# powersupply.net
KiCad netlist of a schematic drawn in Altium Designer
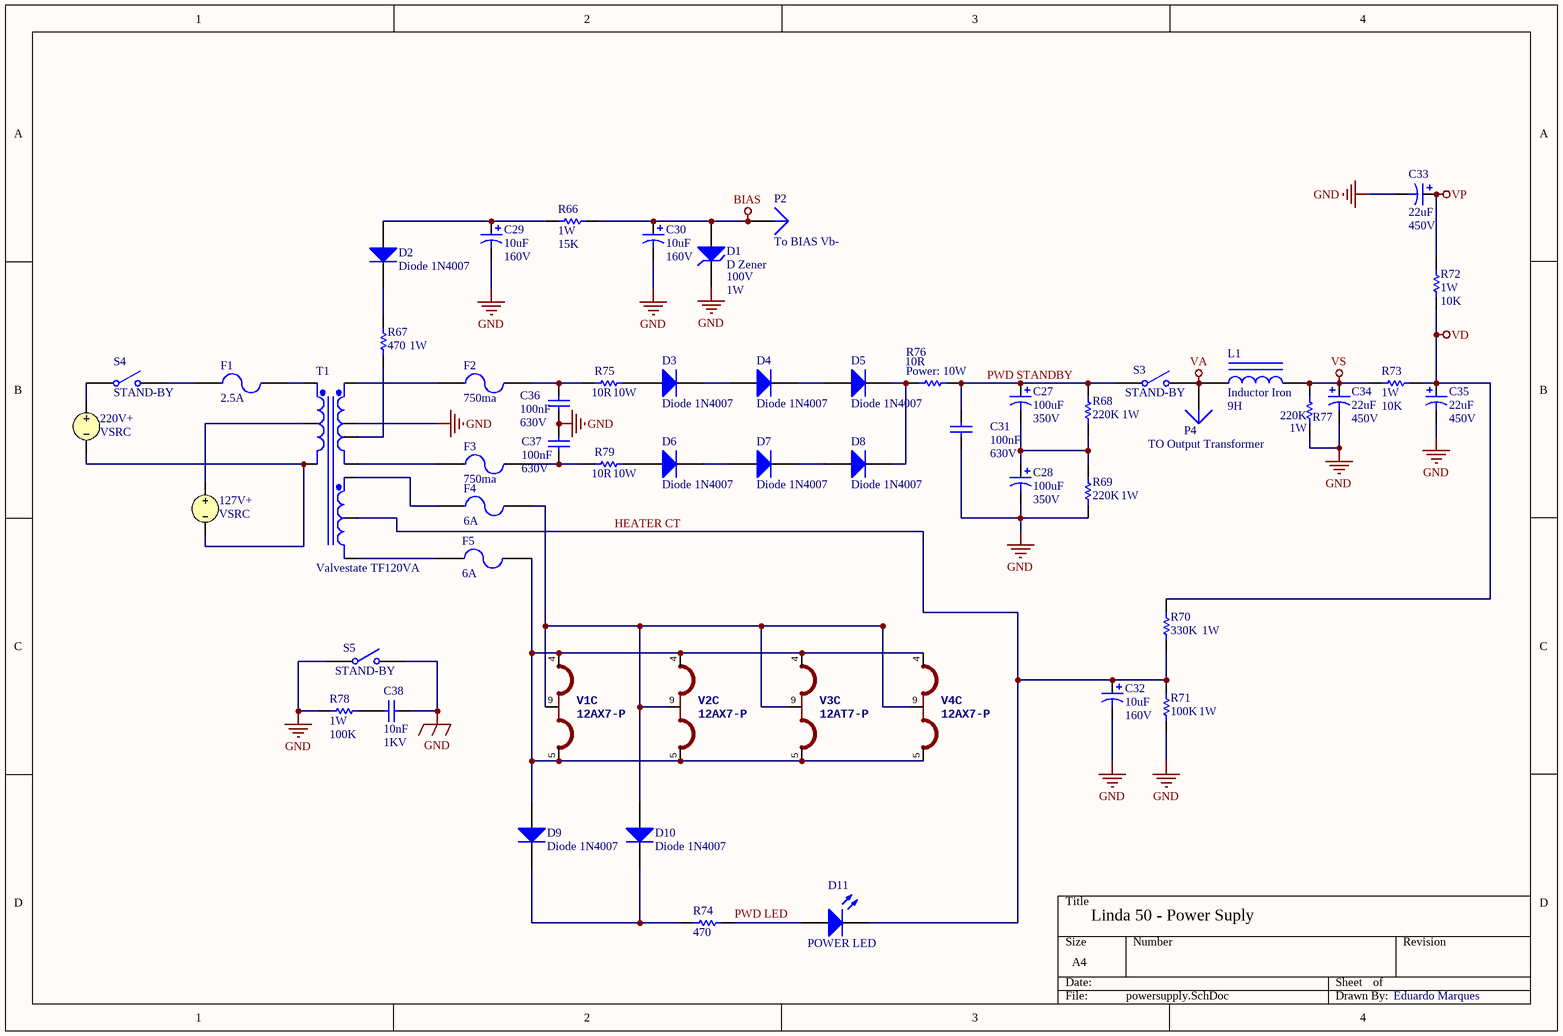
[diagram p0: powersupply.SchDoc]

(export (version "E")
  (design (tool "Eeschema 10.0.6"))
  (components
    (comp (ref "127V+")
      (value "VSRC")
      (description "Voltage Source")
      (fields (field (name "PUBLISHER") "Altium Limited"))
      (libsource (lib "Simulation Sources") (part "VSRC"))
    )
    (comp (ref "220V+")
      (value "VSRC")
      (description "Voltage Source")
      (fields (field (name "PUBLISHER") "Altium Limited"))
      (libsource (lib "Simulation Sources") (part "VSRC"))
    )
    (comp (ref "C27")
      (value "100uF")
      (footprint "FT Eletrolitic 100uF Axial")
      (description "FT Eletrolitic Polarized Capacitor Axial 100uF")
      (fields
        (field (name "VOLTAGE") "350V")
        (field (name "Comment") "Cap FT Eletrolitic 100uF Axial 350V")
        (field (name "PUBLISHER") "Whitesheep Amps")
      )
      (libsource (lib "capacitors") (part "Cap FT Eletrolitic 100uF Axial 350V"))
    )
    (comp (ref "C28")
      (value "100uF")
      (footprint "FT Eletrolitic 100uF Axial")
      (description "FT Eletrolitic Polarized Capacitor Axial 100uF")
      (fields
        (field (name "VOLTAGE") "350V")
        (field (name "Comment") "Cap FT Eletrolitic 100uF Axial 350V")
        (field (name "PUBLISHER") "Whitesheep Amps")
      )
      (libsource (lib "capacitors") (part "Cap FT Eletrolitic 100uF Axial 350V"))
    )
    (comp (ref "C29")
      (value "10uF")
      (footprint "RAD-POL-16x20x7.5")
      (description "Vishay 22uF 100V Polarized Capacitor (Radial); 2 Leads")
      (fields
        (field (name "PART NUMBER") "142 RHS")
        (field (name "VOLTAGE") "160V")
        (field (name "Comment") "Cap Pol Radial Vishay 22uF 100V")
        (field (name "PUBLISHER") "Altium Limited")
      )
      (libsource (lib "capacitors") (part "Cap Pol Radial Vishay 22uF 100V"))
    )
    (comp (ref "C30")
      (value "10uF")
      (footprint "RAD-POL-16x20x7.5")
      (description "Vishay 22uF 100V Polarized Capacitor (Radial); 2 Leads")
      (fields
        (field (name "PART NUMBER") "142 RHS")
        (field (name "VOLTAGE") "160V")
        (field (name "Comment") "Cap Pol Radial Vishay 22uF 100V")
        (field (name "PUBLISHER") "Altium Limited")
      )
      (libsource (lib "capacitors") (part "Cap Pol Radial Vishay 22uF 100V"))
    )
    (comp (ref "C31")
      (value "100nF")
      (footprint "CAP-XICON-100nF-630V")
      (description "Capacitor XICON (WINE COVER) Polypropilene CAP 630V")
      (fields
        (field (name "VOLTAGE") "630V")
        (field (name "Comment") "Orange Drop Capacitor")
        (field (name "PUBLISHER") "Altium Limited")
      )
      (libsource (lib "capacitors") (part "Cap-XICON-100nF-630V"))
    )
    (comp (ref "C32")
      (value "10uF")
      (footprint "RAD-POL-16x20x7.5")
      (description "Vishay 22uF 100V Polarized Capacitor (Radial); 2 Leads")
      (fields
        (field (name "PART NUMBER") "142 RHS")
        (field (name "VOLTAGE") "160V")
        (field (name "Comment") "Cap Pol Radial Vishay 22uF 100V")
        (field (name "PUBLISHER") "Altium Limited")
      )
      (libsource (lib "capacitors") (part "Cap Pol Radial Vishay 22uF 100V"))
    )
    (comp (ref "C33")
      (value "22uF")
      (footprint "RAD-POL-7.6-15")
      (description "Polarized Capacitor (Axial)")
      (fields
        (field (name "VOLTAGE") "450V")
        (field (name "Comment") "Cap Pol Rad")
        (field (name "PUBLISHER") "Altium Limited")
      )
      (libsource (lib "capacitors") (part "Cap Pol Rad"))
    )
    (comp (ref "C34")
      (value "22uF")
      (footprint "RAD-POL-7.6-15")
      (description "Polarized Capacitor (Axial)")
      (fields
        (field (name "VOLTAGE") "450V")
        (field (name "Comment") "Cap Pol Rad")
        (field (name "PUBLISHER") "Altium Limited")
      )
      (libsource (lib "capacitors") (part "Cap Pol Rad"))
    )
    (comp (ref "C35")
      (value "22uF")
      (footprint "RAD-POL-7.6-15")
      (description "Polarized Capacitor (Axial)")
      (fields
        (field (name "VOLTAGE") "450V")
        (field (name "Comment") "Cap Pol Rad")
        (field (name "PUBLISHER") "Altium Limited")
      )
      (libsource (lib "capacitors") (part "Cap Pol Rad"))
    )
    (comp (ref "C36")
      (value "100nF")
      (footprint "CAP-XICON-100nF-630V")
      (description "Capacitor XICON (WINE COVER) Polypropilene CAP 630V")
      (fields
        (field (name "VOLTAGE") "630V")
        (field (name "Comment") "Orange Drop Capacitor")
        (field (name "PUBLISHER") "Altium Limited")
      )
      (libsource (lib "capacitors") (part "Cap-XICON-100nF-630V"))
    )
    (comp (ref "C37")
      (value "100nF")
      (footprint "CAP-XICON-100nF-630V")
      (description "Capacitor XICON (WINE COVER) Polypropilene CAP 630V")
      (fields
        (field (name "VOLTAGE") "630V")
        (field (name "Comment") "Orange Drop Capacitor")
        (field (name "PUBLISHER") "Altium Limited")
      )
      (libsource (lib "capacitors") (part "Cap-XICON-100nF-630V"))
    )
    (comp (ref "C38")
      (value "10nF")
      (footprint "RAD-0.4")
      (description "Capacitor XICON (WINE COVER) Polypropilene CAP 630V")
      (fields
        (field (name "VOLTAGE") "1KV")
        (field (name "Comment") "Orange Drop Capacitor")
        (field (name "PUBLISHER") "Altium Limited")
      )
      (libsource (lib "capacitors") (part "Cap-XICON-100nF-630V"))
    )
    (comp (ref "D1")
      (value "D Zener")
      (footprint "ZENER 1W 100V")
      (description "Zener Diode")
      (fields
        (field (name "VOLTAGE") "100V")
        (field (name "POWER") "1W")
        (field (name "PUBLISHER") "Altium Limited")
      )
      (libsource (lib "Miscellaneous Devices") (part "D Zener"))
    )
    (comp (ref "D2")
      (value "Diode 1N4007")
      (footprint "DO-41")
      (description "1 Amp General Purpose Rectifier")
      (fields (field (name "PUBLISHER") "Altium Limited"))
      (libsource (lib "Miscellaneous Devices") (part "Diode 1N4007"))
    )
    (comp (ref "D3")
      (value "Diode 1N4007")
      (footprint "1N4007-10.46mm Diode")
      (description "1 Amp General Purpose Rectifier")
      (fields (field (name "PUBLISHER") "Altium Limited"))
      (libsource (lib "diodes") (part "Diode 1N4007"))
    )
    (comp (ref "D4")
      (value "Diode 1N4007")
      (footprint "1N4007-10.46mm Diode")
      (description "1 Amp General Purpose Rectifier")
      (fields (field (name "PUBLISHER") "Altium Limited"))
      (libsource (lib "diodes") (part "Diode 1N4007"))
    )
    (comp (ref "D5")
      (value "Diode 1N4007")
      (footprint "1N4007-10.46mm Diode")
      (description "1 Amp General Purpose Rectifier")
      (fields (field (name "PUBLISHER") "Altium Limited"))
      (libsource (lib "diodes") (part "Diode 1N4007"))
    )
    (comp (ref "D6")
      (value "Diode 1N4007")
      (footprint "1N4007-10.46mm Diode")
      (description "1 Amp General Purpose Rectifier")
      (fields (field (name "PUBLISHER") "Altium Limited"))
      (libsource (lib "diodes") (part "Diode 1N4007"))
    )
    (comp (ref "D7")
      (value "Diode 1N4007")
      (footprint "1N4007-10.46mm Diode")
      (description "1 Amp General Purpose Rectifier")
      (fields (field (name "PUBLISHER") "Altium Limited"))
      (libsource (lib "diodes") (part "Diode 1N4007"))
    )
    (comp (ref "D8")
      (value "Diode 1N4007")
      (footprint "1N4007-10.46mm Diode")
      (description "1 Amp General Purpose Rectifier")
      (fields (field (name "PUBLISHER") "Altium Limited"))
      (libsource (lib "diodes") (part "Diode 1N4007"))
    )
    (comp (ref "D9")
      (value "Diode 1N4007")
      (footprint "1N4007-10.46mm Diode")
      (description "1 Amp General Purpose Rectifier")
      (fields (field (name "PUBLISHER") "Altium Limited"))
      (libsource (lib "diodes") (part "Diode 1N4007"))
    )
    (comp (ref "D10")
      (value "Diode 1N4007")
      (footprint "1N4007-10.46mm Diode")
      (description "1 Amp General Purpose Rectifier")
      (fields (field (name "PUBLISHER") "Altium Limited"))
      (libsource (lib "diodes") (part "Diode 1N4007"))
    )
    (comp (ref "D11")
      (value "POWER LED")
      (footprint "LED-1")
      (description "Typical RED GaAs LED")
      (fields (field (name "PUBLISHER") "Altium Limited"))
      (libsource (lib "Miscellaneous Devices") (part "LED1"))
    )
    (comp (ref "F1")
      (value "2.5A")
      (footprint "PIN-W2/E2.8")
      (description "Fuse")
      (fields (field (name "PUBLISHER") "Altium Limited"))
      (libsource (lib "Miscellaneous Devices") (part "Fuse 2"))
    )
    (comp (ref "F2")
      (value "750ma")
      (footprint "FUSE-PCB-6x31")
      (description "Fuse")
      (fields (field (name "PUBLISHER") "Altium Limited"))
      (libsource (lib "fuses") (part "Fuse 2"))
    )
    (comp (ref "F3")
      (value "750ma")
      (footprint "FUSE-PCB-6x31")
      (description "Fuse")
      (fields (field (name "PUBLISHER") "Altium Limited"))
      (libsource (lib "fuses") (part "Fuse 2"))
    )
    (comp (ref "F4")
      (value "6A")
      (footprint "FUSE-PCB-6x31")
      (description "Fuse")
      (fields (field (name "PUBLISHER") "Altium Limited"))
      (libsource (lib "fuses") (part "Fuse 2"))
    )
    (comp (ref "F5")
      (value "6A")
      (footprint "FUSE-PCB-6x31")
      (description "Fuse")
      (fields (field (name "PUBLISHER") "Altium Limited"))
      (libsource (lib "fuses") (part "Fuse 2"))
    )
    (comp (ref "L1")
      (value "Inductor Iron")
      (footprint "AXIAL-0.9")
      (description "Magnetic-Core Inductor")
      (fields (field (name "ALTIUM_VALUE") "9H") (field (name "PUBLISHER") "Altium Limited"))
      (libsource (lib "Miscellaneous Devices") (part "Inductor Iron"))
    )
    (comp (ref "P2")
      (value "To BIAS Vb-")
      (footprint "PIN1")
      (description "Plug")
      (fields (field (name "PUBLISHER") "Altium Limited"))
      (libsource (lib "Miscellaneous Connectors") (part "Plug"))
    )
    (comp (ref "P4")
      (value "TO Output Transformer")
      (footprint "PIN1")
      (description "Plug")
      (fields (field (name "PUBLISHER") "Altium Limited"))
      (libsource (lib "Miscellaneous Connectors") (part "Plug"))
    )
    (comp (ref "R66")
      (value "15K")
      (footprint "AXIAL-0.6")
      (description "Semiconductor Resistor")
      (fields
        (field (name "POWER") "1W")
        (field (name "Comment") "Metal Film Resistor 1W")
        (field (name "PUBLISHER") "Linda Hand Buit Amplifiers")
      )
      (libsource (lib "resistors") (part "Res Wire Wound 1W"))
    )
    (comp (ref "R67")
      (value "470")
      (footprint "AXIAL-0.6")
      (description "Semiconductor Resistor")
      (fields
        (field (name "POWER") "1W")
        (field (name "Comment") "Metal Film Resistor 1W")
        (field (name "PUBLISHER") "Linda Hand Buit Amplifiers")
      )
      (libsource (lib "resistors") (part "Res Wire Wound 1W"))
    )
    (comp (ref "R68")
      (value "220K")
      (footprint "RESISTOR-MetalOxide-3W")
      (description "Semiconductor Resistor")
      (fields
        (field (name "POWER") "1W")
        (field (name "Comment") "Metal Film Resistor 1W")
        (field (name "PUBLISHER") "Linda Hand Buit Amplifiers")
      )
      (libsource (lib "resistors") (part "Res Wire Wound 1W"))
    )
    (comp (ref "R69")
      (value "220K")
      (footprint "RESISTOR-MetalOxide-3W")
      (description "Semiconductor Resistor")
      (fields
        (field (name "POWER") "1W")
        (field (name "Comment") "Metal Film Resistor 1W")
        (field (name "PUBLISHER") "Linda Hand Buit Amplifiers")
      )
      (libsource (lib "resistors") (part "Res Wire Wound 1W"))
    )
    (comp (ref "R70")
      (value "330K")
      (footprint "AXIAL-0.6")
      (description "Semiconductor Resistor")
      (fields
        (field (name "POWER") "1W")
        (field (name "Comment") "Metal Film Resistor 1W")
        (field (name "PUBLISHER") "Linda Hand Buit Amplifiers")
      )
      (libsource (lib "resistors") (part "Res Wire Wound 1W"))
    )
    (comp (ref "R71")
      (value "100K")
      (footprint "AXIAL-0.6")
      (description "Semiconductor Resistor")
      (fields
        (field (name "POWER") "1W")
        (field (name "Comment") "Metal Film Resistor 1W")
        (field (name "PUBLISHER") "Linda Hand Buit Amplifiers")
      )
      (libsource (lib "resistors") (part "Res Wire Wound 1W"))
    )
    (comp (ref "R72")
      (value "10K")
      (footprint "AXIAL-0.6")
      (description "Semiconductor Resistor")
      (fields
        (field (name "POWER") "1W")
        (field (name "Comment") "Metal Film Resistor 1W")
        (field (name "PUBLISHER") "Linda Hand Buit Amplifiers")
      )
      (libsource (lib "resistors") (part "Res Wire Wound 1W"))
    )
    (comp (ref "R73")
      (value "10K")
      (footprint "AXIAL-0.6")
      (description "Semiconductor Resistor")
      (fields
        (field (name "POWER") "1W")
        (field (name "Comment") "Metal Film Resistor 1W")
        (field (name "PUBLISHER") "Linda Hand Buit Amplifiers")
      )
      (libsource (lib "resistors") (part "Res Wire Wound 1W"))
    )
    (comp (ref "R74")
      (value "470")
      (footprint "AXIAL-0.6")
      (description "Semiconductor Resistor")
      (fields
        (field (name "POWER") "1/2W")
        (field (name "Comment") "Metal Film Resistor 1/2W")
        (field (name "PUBLISHER") "Whitesheep Amps")
      )
      (libsource (lib "resistors") (part "Res Metal Film 1/2W"))
    )
    (comp (ref "R75")
      (value "10R")
      (footprint "AXIAL-1.0")
      (description "Semiconductor Resistor")
      (fields
        (field (name "POWER") "10W")
        (field (name "Comment") "Wire Wound Power Resistor")
        (field (name "PUBLISHER") "Whitesheep Amps")
      )
      (libsource (lib "resistors") (part "Res Wire Wound Power Resistor 5W"))
    )
    (comp (ref "R76")
      (value "10R")
      (footprint "Power Wirewound Resistor 10W - Vishay Dale")
      (description "Semiconductor Resistor")
      (fields
        (field (name "POWER") "10W")
        (field (name "MANUFACTURER PART NUMBER") "RS01010R00FE73")
        (field (name "Comment") "Wire Wound Power Resistor")
        (field (name "PUBLISHER") "Whitesheep Amps")
      )
      (libsource (lib "resistors") (part "Res Vishay Dale Wire Wound Power Resistor 10R 10W"))
    )
    (comp (ref "R77")
      (value "220K")
      (footprint "RESISTOR-MetalOxide-3W")
      (description "Semiconductor Resistor")
      (fields
        (field (name "POWER") "1W")
        (field (name "Comment") "Metal Film Resistor 1W")
        (field (name "PUBLISHER") "Linda Hand Buit Amplifiers")
      )
      (libsource (lib "resistors") (part "Res Wire Wound 1W"))
    )
    (comp (ref "R78")
      (value "100K")
      (footprint "AXIAL-0.6")
      (description "Semiconductor Resistor")
      (fields
        (field (name "POWER") "1W")
        (field (name "Comment") "Metal Film Resistor 1W")
        (field (name "PUBLISHER") "Linda Hand Buit Amplifiers")
      )
      (libsource (lib "resistors") (part "Res Wire Wound 1W"))
    )
    (comp (ref "R79")
      (value "10R")
      (footprint "AXIAL-1.0")
      (description "Semiconductor Resistor")
      (fields
        (field (name "POWER") "10W")
        (field (name "Comment") "Wire Wound Power Resistor")
        (field (name "PUBLISHER") "Whitesheep Amps")
      )
      (libsource (lib "resistors") (part "Res Wire Wound Power Resistor 5W"))
    )
    (comp (ref "S3")
      (value "STAND-BY")
      (footprint "SPST-2")
      (description "Single-Pole, Single-Throw Switch")
      (fields (field (name "PUBLISHER") "Altium Limited"))
      (libsource (lib "Miscellaneous Devices") (part "SW-SPST"))
    )
    (comp (ref "S4")
      (value "STAND-BY")
      (footprint "SPST-2")
      (description "Single-Pole, Single-Throw Switch")
      (fields (field (name "PUBLISHER") "Altium Limited"))
      (libsource (lib "Miscellaneous Devices") (part "SW-SPST"))
    )
    (comp (ref "S5")
      (value "STAND-BY")
      (footprint "SPST-2")
      (description "Single-Pole, Single-Throw Switch")
      (fields (field (name "PUBLISHER") "Altium Limited"))
      (libsource (lib "Miscellaneous Devices") (part "SW-SPST"))
    )
    (comp (ref "T1")
      (value "Valvestate TF120VA")
      (footprint "TRF_5")
      (description "VALVESTATE TF 120VA")
      (fields (field (name "PUBLISHER") "LINDA Hand Built Amplifiers"))
      (libsource (lib "trafo") (part "Valvestate TF120VA"))
    )
    (comp (ref "V1")
      (value "12AX7-P")
      (footprint "NOVAL")
      (libsource (lib "eagle_tubes_v6") (part "12AX7-P"))
    )
    (comp (ref "V2")
      (value "12AX7-P")
      (footprint "NOVAL")
      (libsource (lib "eagle_tubes_v6") (part "12AX7-P"))
    )
    (comp (ref "V3")
      (value "12AT7-P")
      (footprint "NOVAL")
      (libsource (lib "eagle_tubes_v6") (part "12AT7-P"))
    )
    (comp (ref "V4")
      (value "12AX7-P")
      (footprint "NOVAL")
      (libsource (lib "eagle_tubes_v6") (part "12AX7-P"))
    )
  )
  (nets
    (net (code "1") (name "/HEATER CT") (class "Default")
      (node (ref "C32") (pin "1") (pinfunction "1_1") (pintype "passive"))
      (node (ref "D11") (pin "2") (pinfunction "K_2") (pintype "passive"))
      (node (ref "R70") (pin "1") (pinfunction "1_1") (pintype "passive"))
      (node (ref "R71") (pin "2") (pinfunction "2_2") (pintype "passive"))
      (node (ref "T1") (pin "9") (pinfunction "3.15V_CT_9") (pintype "passive"))
    )
    (net (code "3") (name "/PWD STANDBY") (class "Default")
      (node (ref "C27") (pin "1") (pinfunction "1_1") (pintype "passive"))
      (node (ref "C31") (pin "2") (pinfunction "2_2") (pintype "passive"))
      (node (ref "R68") (pin "2") (pinfunction "2_2") (pintype "passive"))
      (node (ref "R76") (pin "2") (pinfunction "2_2") (pintype "passive"))
      (node (ref "S3") (pin "1") (pinfunction "COMMON_1") (pintype "passive"))
    )
    (net (code "4") (name "BIAS") (class "Default")
      (node (ref "C30") (pin "1") (pinfunction "1_1") (pintype "passive"))
      (node (ref "D1") (pin "1") (pinfunction "A_1") (pintype "passive"))
      (node (ref "P2") (pin "1") (pinfunction "1_1") (pintype "passive"))
      (node (ref "R66") (pin "1") (pinfunction "1_1") (pintype "passive"))
    )
    (net (code "5") (name "GND") (class "Default")
      (node (ref "C28") (pin "2") (pinfunction "2_2") (pintype "passive"))
      (node (ref "C29") (pin "2") (pinfunction "2_2") (pintype "passive"))
      (node (ref "C30") (pin "2") (pinfunction "2_2") (pintype "passive"))
      (node (ref "C31") (pin "1") (pinfunction "1_1") (pintype "passive"))
      (node (ref "C32") (pin "2") (pinfunction "2_2") (pintype "passive"))
      (node (ref "C33") (pin "2") (pinfunction "2_2") (pintype "passive"))
      (node (ref "C34") (pin "2") (pinfunction "2_2") (pintype "passive"))
      (node (ref "C35") (pin "2") (pinfunction "2_2") (pintype "passive"))
      (node (ref "C36") (pin "1") (pinfunction "1_1") (pintype "passive"))
      (node (ref "C37") (pin "2") (pinfunction "2_2") (pintype "passive"))
      (node (ref "C38") (pin "1") (pinfunction "1_1") (pintype "passive"))
      (node (ref "D1") (pin "2") (pinfunction "K_2") (pintype "passive"))
      (node (ref "R69") (pin "1") (pinfunction "1_1") (pintype "passive"))
      (node (ref "R71") (pin "1") (pinfunction "1_1") (pintype "passive"))
      (node (ref "R77") (pin "1") (pinfunction "1_1") (pintype "passive"))
      (node (ref "R78") (pin "2") (pinfunction "2_2") (pintype "passive"))
      (node (ref "S5") (pin "1") (pinfunction "COMMON_1") (pintype "passive"))
      (node (ref "S5") (pin "2") (pinfunction "NO_2") (pintype "passive"))
      (node (ref "T1") (pin "5") (pinfunction "SEC_CT_5") (pintype "passive"))
    )
    (net (code "6") (name "Net-(C27-Pad2)") (class "Default")
      (node (ref "C27") (pin "2") (pinfunction "2_2") (pintype "passive"))
      (node (ref "C28") (pin "1") (pinfunction "1_1") (pintype "passive"))
      (node (ref "R68") (pin "1") (pinfunction "1_1") (pintype "passive"))
      (node (ref "R69") (pin "2") (pinfunction "2_2") (pintype "passive"))
    )
    (net (code "7") (name "Net-(C36-Pad2)") (class "Default")
      (node (ref "C36") (pin "2") (pinfunction "2_2") (pintype "passive"))
      (node (ref "F2") (pin "2") (pinfunction "2_2") (pintype "passive"))
      (node (ref "R75") (pin "1") (pinfunction "1_1") (pintype "passive"))
    )
    (net (code "8") (name "Net-(C37-Pad1)") (class "Default")
      (node (ref "C37") (pin "1") (pinfunction "1_1") (pintype "passive"))
      (node (ref "F3") (pin "2") (pinfunction "2_2") (pintype "passive"))
      (node (ref "R79") (pin "1") (pinfunction "1_1") (pintype "passive"))
    )
    (net (code "9") (name "Net-(C38-Pad2)") (class "Default")
      (node (ref "C38") (pin "2") (pinfunction "2_2") (pintype "passive"))
      (node (ref "R78") (pin "1") (pinfunction "1_1") (pintype "passive"))
    )
    (net (code "10") (name "Net-(D2-A)") (class "Default")
      (node (ref "C29") (pin "1") (pinfunction "1_1") (pintype "passive"))
      (node (ref "D2") (pin "1") (pinfunction "A_1") (pintype "passive"))
      (node (ref "R66") (pin "2") (pinfunction "2_2") (pintype "passive"))
    )
    (net (code "11") (name "Net-(D2-K)") (class "Default")
      (node (ref "D2") (pin "2") (pinfunction "K_2") (pintype "passive"))
      (node (ref "R67") (pin "2") (pinfunction "2_2") (pintype "passive"))
    )
    (net (code "12") (name "Net-(D3-A)") (class "Default")
      (node (ref "D3") (pin "1") (pinfunction "A_1") (pintype "passive"))
      (node (ref "R75") (pin "2") (pinfunction "2_2") (pintype "passive"))
    )
    (net (code "13") (name "Net-(D3-K)") (class "Default")
      (node (ref "D3") (pin "2") (pinfunction "K_2") (pintype "passive"))
      (node (ref "D4") (pin "1") (pinfunction "A_1") (pintype "passive"))
    )
    (net (code "14") (name "Net-(D4-K)") (class "Default")
      (node (ref "D4") (pin "2") (pinfunction "K_2") (pintype "passive"))
      (node (ref "D5") (pin "1") (pinfunction "A_1") (pintype "passive"))
    )
    (net (code "15") (name "Net-(D5-K)") (class "Default")
      (node (ref "D5") (pin "2") (pinfunction "K_2") (pintype "passive"))
      (node (ref "D8") (pin "2") (pinfunction "K_2") (pintype "passive"))
      (node (ref "R76") (pin "1") (pinfunction "1_1") (pintype "passive"))
    )
    (net (code "16") (name "Net-(D6-A)") (class "Default")
      (node (ref "D6") (pin "1") (pinfunction "A_1") (pintype "passive"))
      (node (ref "R79") (pin "2") (pinfunction "2_2") (pintype "passive"))
    )
    (net (code "17") (name "Net-(D6-K)") (class "Default")
      (node (ref "D6") (pin "2") (pinfunction "K_2") (pintype "passive"))
      (node (ref "D7") (pin "1") (pinfunction "A_1") (pintype "passive"))
    )
    (net (code "18") (name "Net-(D7-K)") (class "Default")
      (node (ref "D7") (pin "2") (pinfunction "K_2") (pintype "passive"))
      (node (ref "D8") (pin "1") (pinfunction "A_1") (pintype "passive"))
    )
    (net (code "19") (name "Net-(D9-A)") (class "Default")
      (node (ref "D9") (pin "1") (pinfunction "A_1") (pintype "passive"))
      (node (ref "F5") (pin "2") (pinfunction "2_2") (pintype "passive"))
      (node (ref "V1") (pin "4") (pinfunction "H1_4") (pintype "passive"))
      (node (ref "V1") (pin "5") (pinfunction "H3_5") (pintype "passive"))
      (node (ref "V2") (pin "4") (pinfunction "H1_4") (pintype "passive"))
      (node (ref "V2") (pin "5") (pinfunction "H3_5") (pintype "passive"))
      (node (ref "V3") (pin "4") (pinfunction "H1_4") (pintype "passive"))
      (node (ref "V3") (pin "5") (pinfunction "H3_5") (pintype "passive"))
      (node (ref "V4") (pin "4") (pinfunction "H1_4") (pintype "passive"))
      (node (ref "V4") (pin "5") (pinfunction "H3_5") (pintype "passive"))
    )
    (net (code "20") (name "Net-(D10-A)") (class "Default")
      (node (ref "D10") (pin "1") (pinfunction "A_1") (pintype "passive"))
      (node (ref "F4") (pin "2") (pinfunction "2_2") (pintype "passive"))
      (node (ref "V1") (pin "9") (pinfunction "H2_9") (pintype "passive"))
      (node (ref "V2") (pin "9") (pinfunction "H2_9") (pintype "passive"))
      (node (ref "V3") (pin "9") (pinfunction "H2_9") (pintype "passive"))
      (node (ref "V4") (pin "9") (pinfunction "H2_9") (pintype "passive"))
    )
    (net (code "21") (name "Net-(D10-K)") (class "Default")
      (node (ref "D10") (pin "2") (pinfunction "K_2") (pintype "passive"))
      (node (ref "D9") (pin "2") (pinfunction "K_2") (pintype "passive"))
      (node (ref "R74") (pin "1") (pinfunction "1_1") (pintype "passive"))
    )
    (net (code "22") (name "Net-(D11-A)") (class "Default")
      (node (ref "D11") (pin "1") (pinfunction "A_1") (pintype "passive"))
      (node (ref "R74") (pin "2") (pinfunction "2_2") (pintype "passive"))
    )
    (net (code "23") (name "Net-(S4-COMMON)") (class "Default")
      (node (ref "220V+") (pin "1") (pinfunction "1_1") (pintype "passive"))
      (node (ref "S4") (pin "1") (pinfunction "COMMON_1") (pintype "passive"))
    )
    (net (code "24") (name "Net-(S4-NO)") (class "Default")
      (node (ref "F1") (pin "1") (pinfunction "1_1") (pintype "passive"))
      (node (ref "S4") (pin "2") (pinfunction "NO_2") (pintype "passive"))
    )
    (net (code "25") (name "Net-(T1-3.15V+)") (class "Default")
      (node (ref "F4") (pin "1") (pinfunction "1_1") (pintype "passive"))
      (node (ref "T1") (pin "8") (pinfunction "3.15V+_8") (pintype "passive"))
    )
    (net (code "26") (name "Net-(T1-3.15V_-)") (class "Default")
      (node (ref "F5") (pin "1") (pinfunction "1_1") (pintype "passive"))
      (node (ref "T1") (pin "10") (pinfunction "3.15V_-_10") (pintype "passive"))
    )
    (net (code "27") (name "Net-(T1-Pri+220V)") (class "Default")
      (node (ref "F1") (pin "2") (pinfunction "2_2") (pintype "passive"))
      (node (ref "T1") (pin "1") (pinfunction "Pri+220V_1") (pintype "passive"))
    )
    (net (code "28") (name "Net-(T1-Pri+_127V)") (class "Default")
      (node (ref "127V+") (pin "1") (pinfunction "1_1") (pintype "passive"))
      (node (ref "T1") (pin "2") (pinfunction "Pri+_127V_2") (pintype "passive"))
    )
    (net (code "29") (name "Net-(T1-Pri-)") (class "Default")
      (node (ref "127V+") (pin "2") (pinfunction "2_2") (pintype "passive"))
      (node (ref "220V+") (pin "2") (pinfunction "2_2") (pintype "passive"))
      (node (ref "T1") (pin "3") (pinfunction "Pri-_3") (pintype "passive"))
    )
    (net (code "30") (name "Net-(T1-Sec_55V_+)") (class "Default")
      (node (ref "R67") (pin "1") (pinfunction "1_1") (pintype "passive"))
      (node (ref "T1") (pin "6") (pinfunction "Sec_55V_+_6") (pintype "passive"))
    )
    (net (code "31") (name "Net-(T1-Sec_355V_+)") (class "Default")
      (node (ref "F2") (pin "1") (pinfunction "1_1") (pintype "passive"))
      (node (ref "T1") (pin "4") (pinfunction "Sec_355V_+_4") (pintype "passive"))
    )
    (net (code "32") (name "Net-(T1-Sec_355V_-)") (class "Default")
      (node (ref "F3") (pin "1") (pinfunction "1_1") (pintype "passive"))
      (node (ref "T1") (pin "7") (pinfunction "Sec_355V_-_7") (pintype "passive"))
    )
    (net (code "33") (name "VA") (class "Default")
      (node (ref "L1") (pin "1") (pinfunction "1_1") (pintype "passive"))
      (node (ref "P4") (pin "1") (pinfunction "1_1") (pintype "passive"))
      (node (ref "S3") (pin "2") (pinfunction "NO_2") (pintype "passive"))
    )
    (net (code "34") (name "VD") (class "Default")
      (node (ref "C35") (pin "1") (pinfunction "1_1") (pintype "passive"))
      (node (ref "R70") (pin "2") (pinfunction "2_2") (pintype "passive"))
      (node (ref "R72") (pin "2") (pinfunction "2_2") (pintype "passive"))
      (node (ref "R73") (pin "1") (pinfunction "1_1") (pintype "passive"))
    )
    (net (code "35") (name "VP") (class "Default")
      (node (ref "C33") (pin "1") (pinfunction "1_1") (pintype "passive"))
      (node (ref "R72") (pin "1") (pinfunction "1_1") (pintype "passive"))
    )
    (net (code "36") (name "VS") (class "Default")
      (node (ref "C34") (pin "1") (pinfunction "1_1") (pintype "passive"))
      (node (ref "L1") (pin "2") (pinfunction "2_2") (pintype "passive"))
      (node (ref "R73") (pin "2") (pinfunction "2_2") (pintype "passive"))
      (node (ref "R77") (pin "2") (pinfunction "2_2") (pintype "passive"))
    )
  )
)
